# TCA8418_rev_B.net
KiCad netlist of a schematic drawn in EAGLE
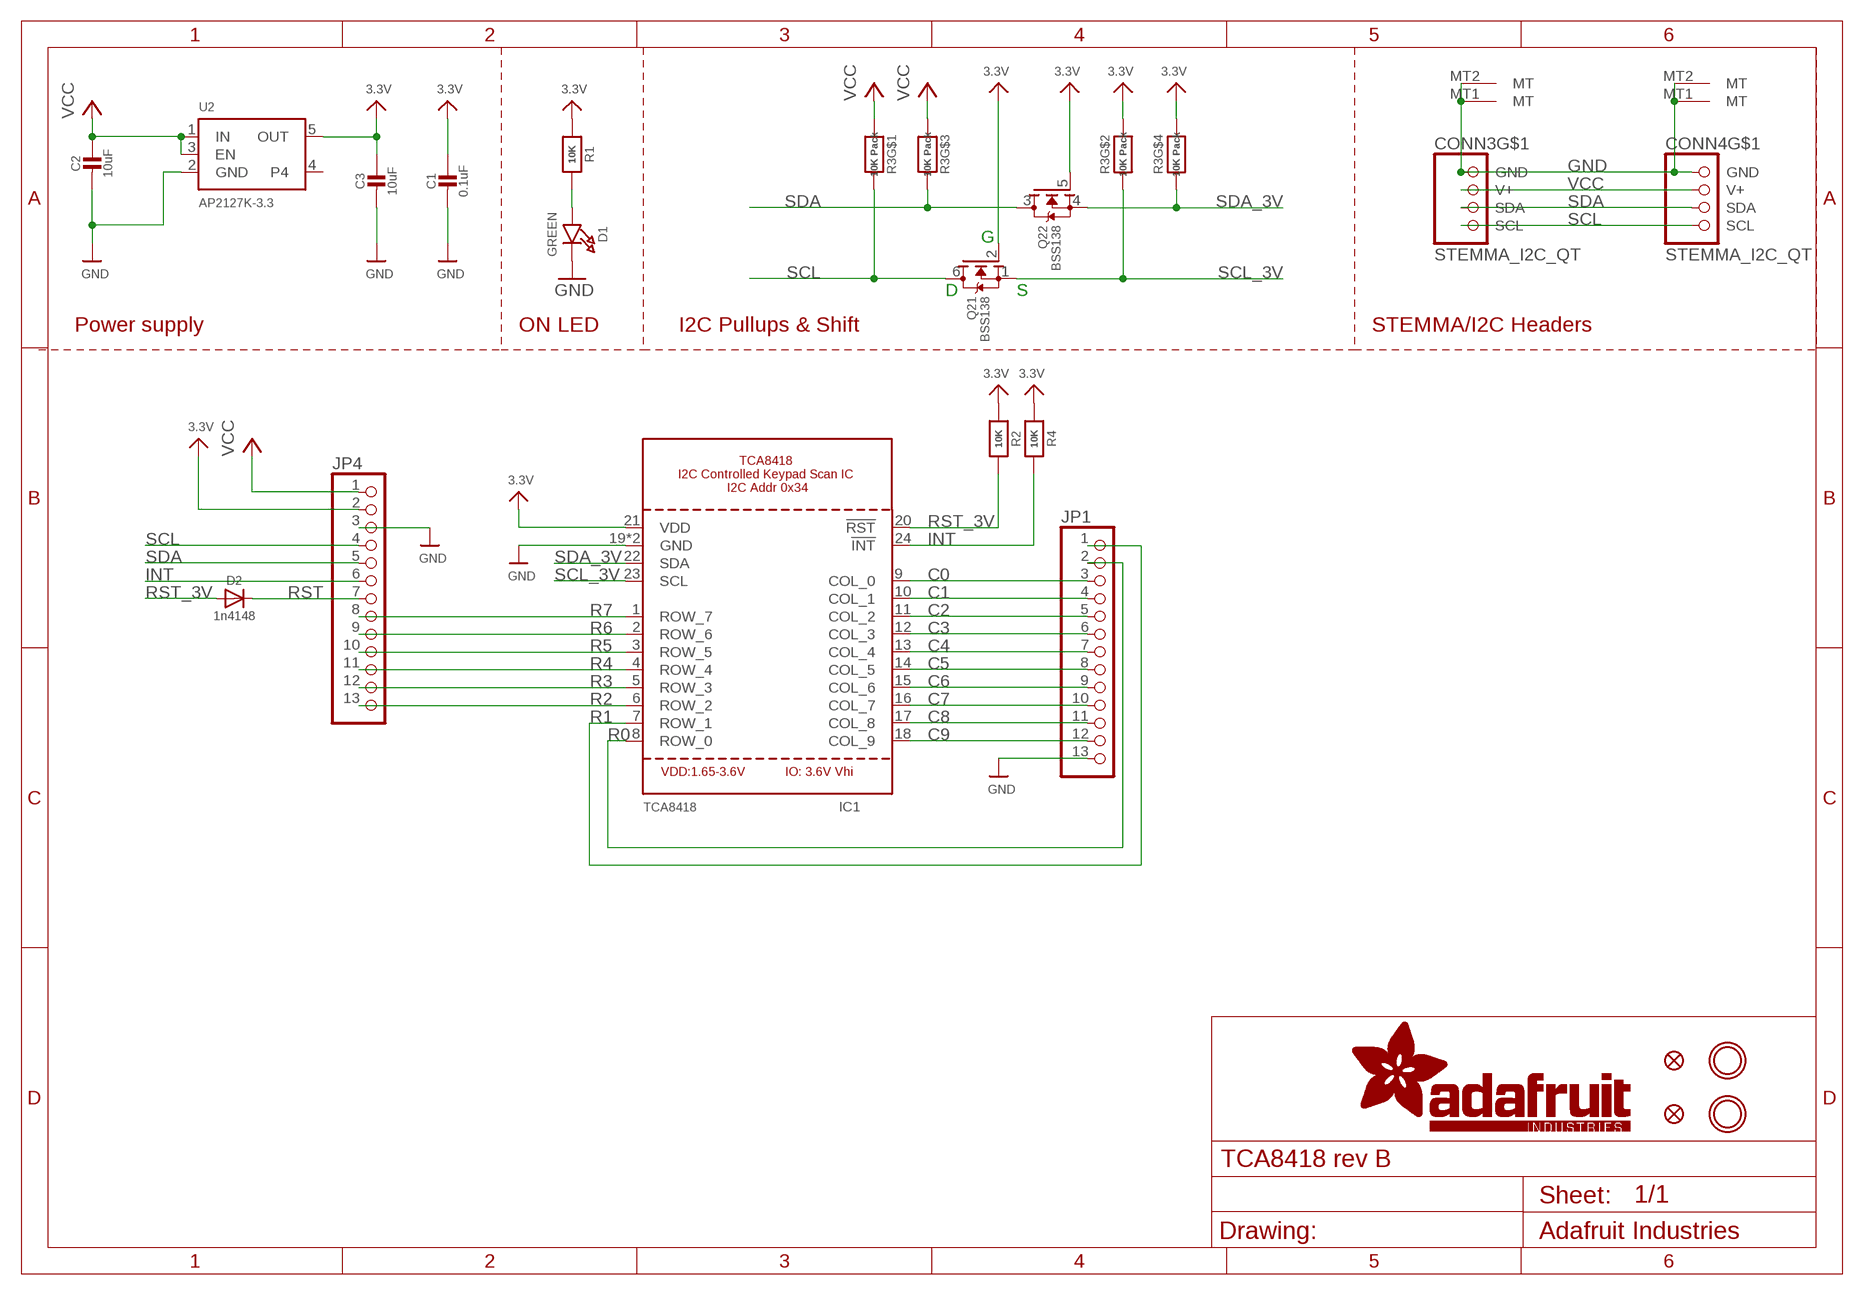
[diagram p0: schematic, sheet 1]

(export (version "E")
  (design (tool "Eeschema 10.0.6"))
  (components
    (comp (ref "C1")
      (value "0.1uF")
      (footprint "eagle-import:0603-NO")
      (libsource (lib "eagle-import") (part "CAP_CERAMIC0603_NO"))
    )
    (comp (ref "C2")
      (value "10uF")
      (footprint "eagle-import:0805-NO")
      (libsource (lib "eagle-import") (part "CAP_CERAMIC0805-NOOUTLINE"))
    )
    (comp (ref "C3")
      (value "10uF")
      (footprint "eagle-import:0805-NO")
      (libsource (lib "eagle-import") (part "CAP_CERAMIC0805-NOOUTLINE"))
    )
    (comp (ref "CONN3")
      (value "STEMMA_I2C_QT")
      (footprint "eagle-import:JST_SH4")
      (libsource (lib "eagle-import") (part "STEMMA_I2C_QT"))
    )
    (comp (ref "CONN4")
      (value "STEMMA_I2C_QT")
      (footprint "eagle-import:JST_SH4")
      (libsource (lib "eagle-import") (part "STEMMA_I2C_QT"))
    )
    (comp (ref "D1")
      (value "GREEN")
      (footprint "eagle-import:CHIPLED_0603_NOOUTLINE")
      (libsource (lib "eagle-import") (part "LED0603_NOOUTLINE"))
    )
    (comp (ref "D2")
      (value "1n4148")
      (footprint "eagle-import:SOD-323")
      (libsource (lib "eagle-import") (part "DIODESOD-323"))
    )
    (comp (ref "FID3")
      (value "FIDUCIAL_1MM")
      (footprint "eagle-import:FIDUCIAL_1MM")
      (libsource (lib "eagle-import") (part "FIDUCIAL_1MM"))
    )
    (comp (ref "FID4")
      (value "FIDUCIAL_1MM")
      (footprint "eagle-import:FIDUCIAL_1MM")
      (libsource (lib "eagle-import") (part "FIDUCIAL_1MM"))
    )
    (comp (ref "IC1")
      (value "TCA8418")
      (footprint "eagle-import:QFN24_4MM_SMSC")
      (libsource (lib "eagle-import") (part "TCA8418"))
    )
    (comp (ref "JP1")
      (value "HEADER-1X13")
      (footprint "eagle-import:1X13_ROUND_70")
      (libsource (lib "eagle-import") (part "HEADER-1X13"))
    )
    (comp (ref "JP4")
      (value "HEADER-1X13")
      (footprint "eagle-import:1X13_ROUND_70")
      (libsource (lib "eagle-import") (part "HEADER-1X13"))
    )
    (comp (ref "Q2")
      (value "BSS138")
      (footprint "eagle-import:SOT363")
      (libsource (lib "eagle-import") (part "MOSFET-N_DUAL"))
    )
    (comp (ref "R1")
      (value "10K")
      (footprint "eagle-import:0603-NO")
      (libsource (lib "eagle-import") (part "RESISTOR_0603_NOOUT"))
    )
    (comp (ref "R2")
      (value "10K")
      (footprint "eagle-import:0603-NO")
      (libsource (lib "eagle-import") (part "RESISTOR_0603_NOOUT"))
    )
    (comp (ref "R3")
      (value "10K Pack")
      (footprint "eagle-import:RESPACK_4X0603")
      (libsource (lib "eagle-import") (part "RESISTOR_4PACK"))
    )
    (comp (ref "R4")
      (value "10K")
      (footprint "eagle-import:0603-NO")
      (libsource (lib "eagle-import") (part "RESISTOR_0603_NOOUT"))
    )
    (comp (ref "U$1")
      (value "MOUNTINGHOLE2.5")
      (footprint "eagle-import:MOUNTINGHOLE_2.5_PLATED")
      (libsource (lib "eagle-import") (part "MOUNTINGHOLE2.5"))
    )
    (comp (ref "U$17")
      (value "MOUNTINGHOLE2.5")
      (footprint "eagle-import:MOUNTINGHOLE_2.5_PLATED")
      (libsource (lib "eagle-import") (part "MOUNTINGHOLE2.5"))
    )
    (comp (ref "U2")
      (value "AP2127K-3.3")
      (footprint "eagle-import:SOT23-5")
      (libsource (lib "eagle-import") (part "VREG_SOT23-5"))
    )
  )
  (nets
    (net (code "1") (name "/C0") (class "Default")
      (node (ref "IC1") (pin "9") (pinfunction "COL_0_9") (pintype "bidirectional"))
      (node (ref "JP1") (pin "3") (pinfunction "3_3") (pintype "passive"))
    )
    (net (code "2") (name "/C1") (class "Default")
      (node (ref "IC1") (pin "10") (pinfunction "COL_1_10") (pintype "bidirectional"))
      (node (ref "JP1") (pin "4") (pinfunction "4_4") (pintype "passive"))
    )
    (net (code "3") (name "/C2") (class "Default")
      (node (ref "IC1") (pin "11") (pinfunction "COL_2_11") (pintype "bidirectional"))
      (node (ref "JP1") (pin "5") (pinfunction "5_5") (pintype "passive"))
    )
    (net (code "4") (name "/C3") (class "Default")
      (node (ref "IC1") (pin "12") (pinfunction "COL_3_12") (pintype "bidirectional"))
      (node (ref "JP1") (pin "6") (pinfunction "6_6") (pintype "passive"))
    )
    (net (code "5") (name "/C4") (class "Default")
      (node (ref "IC1") (pin "13") (pinfunction "COL_4_13") (pintype "bidirectional"))
      (node (ref "JP1") (pin "7") (pinfunction "7_7") (pintype "passive"))
    )
    (net (code "6") (name "/C5") (class "Default")
      (node (ref "IC1") (pin "14") (pinfunction "COL_5_14") (pintype "bidirectional"))
      (node (ref "JP1") (pin "8") (pinfunction "8_8") (pintype "passive"))
    )
    (net (code "7") (name "/C6") (class "Default")
      (node (ref "IC1") (pin "15") (pinfunction "COL_6_15") (pintype "bidirectional"))
      (node (ref "JP1") (pin "9") (pinfunction "9_9") (pintype "passive"))
    )
    (net (code "8") (name "/C7") (class "Default")
      (node (ref "IC1") (pin "16") (pinfunction "COL_7_16") (pintype "bidirectional"))
      (node (ref "JP1") (pin "10") (pinfunction "10_10") (pintype "passive"))
    )
    (net (code "9") (name "/C8") (class "Default")
      (node (ref "IC1") (pin "17") (pinfunction "COL_8_17") (pintype "bidirectional"))
      (node (ref "JP1") (pin "11") (pinfunction "11_11") (pintype "passive"))
    )
    (net (code "10") (name "/C9") (class "Default")
      (node (ref "IC1") (pin "18") (pinfunction "COL_9_18") (pintype "bidirectional"))
      (node (ref "JP1") (pin "12") (pinfunction "12_12") (pintype "passive"))
    )
    (net (code "11") (name "/INT") (class "Default")
      (node (ref "IC1") (pin "24") (pinfunction "~{INT}_24") (pintype "output"))
      (node (ref "JP4") (pin "6") (pinfunction "6_6") (pintype "passive"))
      (node (ref "R4") (pin "2") (pinfunction "2_2") (pintype "passive"))
    )
    (net (code "12") (name "/R0") (class "Default")
      (node (ref "IC1") (pin "8") (pinfunction "ROW_0_8") (pintype "bidirectional"))
      (node (ref "JP1") (pin "2") (pinfunction "2_2") (pintype "passive"))
    )
    (net (code "13") (name "/R1") (class "Default")
      (node (ref "IC1") (pin "7") (pinfunction "ROW_1_7") (pintype "bidirectional"))
      (node (ref "JP1") (pin "1") (pinfunction "1_1") (pintype "passive"))
    )
    (net (code "14") (name "/R2") (class "Default")
      (node (ref "IC1") (pin "6") (pinfunction "ROW_2_6") (pintype "bidirectional"))
      (node (ref "JP4") (pin "13") (pinfunction "13_13") (pintype "passive"))
    )
    (net (code "15") (name "/R3") (class "Default")
      (node (ref "IC1") (pin "5") (pinfunction "ROW_3_5") (pintype "bidirectional"))
      (node (ref "JP4") (pin "12") (pinfunction "12_12") (pintype "passive"))
    )
    (net (code "16") (name "/R4") (class "Default")
      (node (ref "IC1") (pin "4") (pinfunction "ROW_4_4") (pintype "bidirectional"))
      (node (ref "JP4") (pin "11") (pinfunction "11_11") (pintype "passive"))
    )
    (net (code "17") (name "/R5") (class "Default")
      (node (ref "IC1") (pin "3") (pinfunction "ROW_5_3") (pintype "bidirectional"))
      (node (ref "JP4") (pin "10") (pinfunction "10_10") (pintype "passive"))
    )
    (net (code "18") (name "/R6") (class "Default")
      (node (ref "IC1") (pin "2") (pinfunction "ROW_6_2") (pintype "bidirectional"))
      (node (ref "JP4") (pin "9") (pinfunction "9_9") (pintype "passive"))
    )
    (net (code "19") (name "/R7") (class "Default")
      (node (ref "IC1") (pin "1") (pinfunction "ROW_7_1") (pintype "bidirectional"))
      (node (ref "JP4") (pin "8") (pinfunction "8_8") (pintype "passive"))
    )
    (net (code "20") (name "/RST") (class "Default")
      (node (ref "D2") (pin "C") (pinfunction "C_C") (pintype "passive"))
      (node (ref "JP4") (pin "7") (pinfunction "7_7") (pintype "passive"))
    )
    (net (code "21") (name "/RST_3V") (class "Default")
      (node (ref "D2") (pin "A") (pinfunction "A_A") (pintype "passive"))
      (node (ref "IC1") (pin "20") (pinfunction "~{RST}_20") (pintype "input"))
      (node (ref "R2") (pin "2") (pinfunction "2_2") (pintype "passive"))
    )
    (net (code "22") (name "/SCL") (class "Default")
      (node (ref "CONN3") (pin "4") (pinfunction "SCL_4") (pintype "passive"))
      (node (ref "CONN4") (pin "4") (pinfunction "SCL_4") (pintype "passive"))
      (node (ref "JP4") (pin "4") (pinfunction "4_4") (pintype "passive"))
      (node (ref "Q2") (pin "6") (pinfunction "D_6") (pintype "bidirectional"))
      (node (ref "R3") (pin "8") (pinfunction "2_8") (pintype "passive"))
    )
    (net (code "23") (name "/SCL_3V") (class "Default")
      (node (ref "IC1") (pin "23") (pinfunction "SCL_23") (pintype "bidirectional"))
      (node (ref "Q2") (pin "1") (pinfunction "S_1") (pintype "bidirectional"))
      (node (ref "R3") (pin "7") (pinfunction "2_7") (pintype "passive"))
    )
    (net (code "24") (name "/SDA") (class "Default")
      (node (ref "CONN3") (pin "3") (pinfunction "SDA_3") (pintype "passive"))
      (node (ref "CONN4") (pin "3") (pinfunction "SDA_3") (pintype "passive"))
      (node (ref "JP4") (pin "5") (pinfunction "5_5") (pintype "passive"))
      (node (ref "Q2") (pin "3") (pinfunction "D_3") (pintype "bidirectional"))
      (node (ref "R3") (pin "6") (pinfunction "2_6") (pintype "passive"))
    )
    (net (code "25") (name "/SDA_3V") (class "Default")
      (node (ref "IC1") (pin "22") (pinfunction "SDA_22") (pintype "bidirectional"))
      (node (ref "Q2") (pin "4") (pinfunction "S_4") (pintype "bidirectional"))
      (node (ref "R3") (pin "5") (pinfunction "2_5") (pintype "passive"))
    )
    (net (code "26") (name "3.3V") (class "Default")
      (node (ref "C1") (pin "1") (pinfunction "1_1") (pintype "passive"))
      (node (ref "C3") (pin "1") (pinfunction "1_1") (pintype "passive"))
      (node (ref "IC1") (pin "21") (pinfunction "VDD_21") (pintype "power_in"))
      (node (ref "JP4") (pin "2") (pinfunction "2_2") (pintype "passive"))
      (node (ref "Q2") (pin "2") (pinfunction "G_2") (pintype "bidirectional"))
      (node (ref "Q2") (pin "5") (pinfunction "G_5") (pintype "bidirectional"))
      (node (ref "R1") (pin "1") (pinfunction "1_1") (pintype "passive"))
      (node (ref "R2") (pin "1") (pinfunction "1_1") (pintype "passive"))
      (node (ref "R3") (pin "2") (pinfunction "1_2") (pintype "passive"))
      (node (ref "R3") (pin "4") (pinfunction "1_4") (pintype "passive"))
      (node (ref "R4") (pin "1") (pinfunction "1_1") (pintype "passive"))
      (node (ref "U2") (pin "5") (pinfunction "OUT_5") (pintype "power_in"))
    )
    (net (code "27") (name "GND") (class "Default")
      (node (ref "C1") (pin "2") (pinfunction "2_2") (pintype "passive"))
      (node (ref "C2") (pin "2") (pinfunction "2_2") (pintype "passive"))
      (node (ref "C3") (pin "2") (pinfunction "2_2") (pintype "passive"))
      (node (ref "CONN3") (pin "1") (pinfunction "GND_1") (pintype "passive"))
      (node (ref "CONN3") (pin "MT1") (pinfunction "MT_MT1") (pintype "bidirectional"))
      (node (ref "CONN3") (pin "MT2") (pinfunction "MT_MT2") (pintype "bidirectional"))
      (node (ref "CONN4") (pin "1") (pinfunction "GND_1") (pintype "passive"))
      (node (ref "CONN4") (pin "MT1") (pinfunction "MT_MT1") (pintype "bidirectional"))
      (node (ref "CONN4") (pin "MT2") (pinfunction "MT_MT2") (pintype "bidirectional"))
      (node (ref "D1") (pin "C") (pinfunction "C_C") (pintype "passive"))
      (node (ref "IC1") (pin "19") (pinfunction "GND_19") (pintype "power_in"))
      (node (ref "IC1") (pin "THERM") (pinfunction "GND_THERM") (pintype "power_in"))
      (node (ref "JP1") (pin "13") (pinfunction "13_13") (pintype "passive"))
      (node (ref "JP4") (pin "3") (pinfunction "3_3") (pintype "passive"))
      (node (ref "U2") (pin "2") (pinfunction "GND_2") (pintype "power_in"))
    )
    (net (code "28") (name "Net-(D1-PadA)") (class "Default")
      (node (ref "D1") (pin "A") (pinfunction "A_A") (pintype "passive"))
      (node (ref "R1") (pin "2") (pinfunction "2_2") (pintype "passive"))
    )
    (net (code "29") (name "VCC") (class "Default")
      (node (ref "C2") (pin "1") (pinfunction "1_1") (pintype "passive"))
      (node (ref "CONN3") (pin "2") (pinfunction "V+_2") (pintype "passive"))
      (node (ref "CONN4") (pin "2") (pinfunction "V+_2") (pintype "passive"))
      (node (ref "JP4") (pin "1") (pinfunction "1_1") (pintype "passive"))
      (node (ref "R3") (pin "1") (pinfunction "1_1") (pintype "passive"))
      (node (ref "R3") (pin "3") (pinfunction "1_3") (pintype "passive"))
      (node (ref "U2") (pin "1") (pinfunction "IN_1") (pintype "power_in"))
      (node (ref "U2") (pin "3") (pinfunction "EN_3") (pintype "input"))
    )
    (net (code "30") (name "unconnected-(U2-P4-Pad4)") (class "Default")
      (node (ref "U2") (pin "4") (pinfunction "P4_4") (pintype "bidirectional"))
    )
  )
)
